# Adafruit_Feather_M0_Adalogger.net
KiCad netlist of a schematic drawn in EAGLE
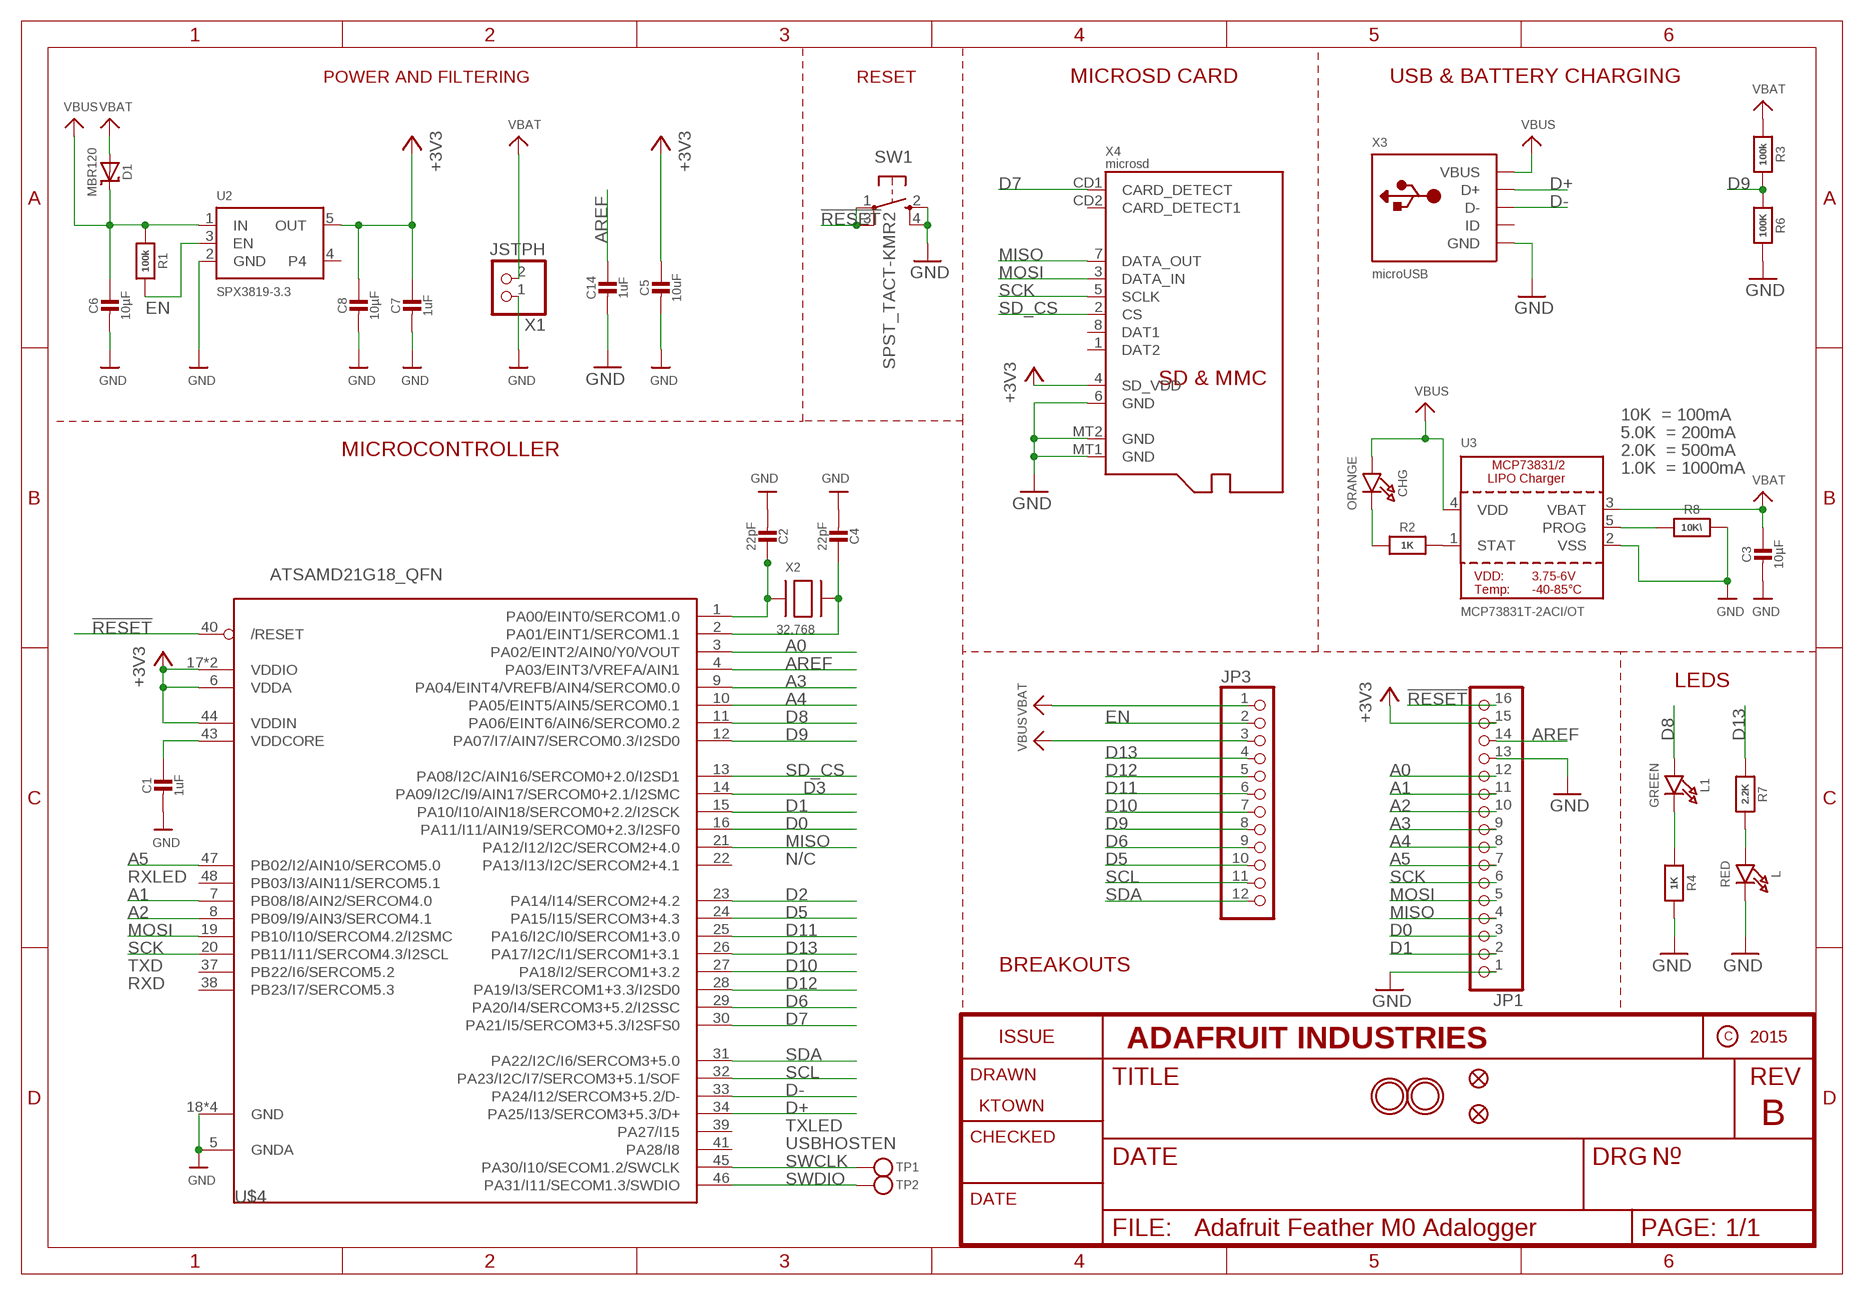
[diagram p0: schematic, sheet 1]

(export (version "E")
  (design (tool "Eeschema 10.0.6"))
  (components
    (comp (ref "C1")
      (value "1uF")
      (footprint "eagle-import:0603-NO")
      (libsource (lib "eagle-import") (part "CAP_CERAMIC0603_NO"))
    )
    (comp (ref "C2")
      (value "22pF")
      (footprint "eagle-import:0603-NO")
      (libsource (lib "eagle-import") (part "CAP_CERAMIC0603_NO"))
    )
    (comp (ref "C3")
      (value "10µF")
      (footprint "eagle-import:0805-NO")
      (libsource (lib "eagle-import") (part "CAP_CERAMIC0805-NOOUTLINE"))
    )
    (comp (ref "C4")
      (value "22pF")
      (footprint "eagle-import:0603-NO")
      (libsource (lib "eagle-import") (part "CAP_CERAMIC0603_NO"))
    )
    (comp (ref "C5")
      (value "10uF")
      (footprint "eagle-import:0805-NO")
      (libsource (lib "eagle-import") (part "CAP_CERAMIC0805-NOOUTLINE"))
    )
    (comp (ref "C6")
      (value "10µF")
      (footprint "eagle-import:0805-NO")
      (libsource (lib "eagle-import") (part "CAP_CERAMIC0805-NOOUTLINE"))
    )
    (comp (ref "C7")
      (value "1uF")
      (footprint "eagle-import:0603-NO")
      (libsource (lib "eagle-import") (part "CAP_CERAMIC0603_NO"))
    )
    (comp (ref "C8")
      (value "10µF")
      (footprint "eagle-import:0805-NO")
      (libsource (lib "eagle-import") (part "CAP_CERAMIC0805-NOOUTLINE"))
    )
    (comp (ref "C14")
      (value "1uF")
      (footprint "eagle-import:0603-NO")
      (libsource (lib "eagle-import") (part "CAP_CERAMIC0603_NO"))
    )
    (comp (ref "CHG")
      (value "ORANGE")
      (footprint "eagle-import:CHIPLED_0805_NOOUTLINE")
      (libsource (lib "eagle-import") (part "LED0805_NOOUTLINE"))
    )
    (comp (ref "D1")
      (value "MBR120")
      (footprint "eagle-import:SOD-123")
      (libsource (lib "eagle-import") (part "DIODE-SCHOTTKYSOD-123"))
    )
    (comp (ref "JP1")
      (value "HEADER-1X16ROUND")
      (footprint "eagle-import:1X16_ROUND")
      (libsource (lib "eagle-import") (part "HEADER-1X16ROUND"))
    )
    (comp (ref "JP3")
      (value "HEADER-1X12")
      (footprint "eagle-import:1X12_ROUND")
      (libsource (lib "eagle-import") (part "HEADER-1X12"))
    )
    (comp (ref "L")
      (value "RED")
      (footprint "eagle-import:CHIPLED_0805_NOOUTLINE")
      (libsource (lib "eagle-import") (part "LED0805_NOOUTLINE"))
    )
    (comp (ref "L1")
      (value "GREEN")
      (footprint "eagle-import:CHIPLED_0805_NOOUTLINE")
      (libsource (lib "eagle-import") (part "LED0805_NOOUTLINE"))
    )
    (comp (ref "R1")
      (value "100k")
      (footprint "eagle-import:0603-NO")
      (libsource (lib "eagle-import") (part "RESISTOR_0603_NOOUT"))
    )
    (comp (ref "R2")
      (value "1K")
      (footprint "eagle-import:0603-NO")
      (libsource (lib "eagle-import") (part "RESISTOR_0603_NOOUT"))
    )
    (comp (ref "R3")
      (value "100k")
      (footprint "eagle-import:0603-NO")
      (libsource (lib "eagle-import") (part "RESISTOR_0603_NOOUT"))
    )
    (comp (ref "R4")
      (value "1K")
      (footprint "eagle-import:0603-NO")
      (libsource (lib "eagle-import") (part "RESISTOR_0603_NOOUT"))
    )
    (comp (ref "R6")
      (value "100K")
      (footprint "eagle-import:0603-NO")
      (libsource (lib "eagle-import") (part "RESISTOR_0603_NOOUT"))
    )
    (comp (ref "R7")
      (value "2.2K")
      (footprint "eagle-import:0603-NO")
      (libsource (lib "eagle-import") (part "RESISTOR_0603_NOOUT"))
    )
    (comp (ref "R8")
      (value "10K\\")
      (footprint "eagle-import:0603-NO")
      (libsource (lib "eagle-import") (part "RESISTOR_0603_NOOUT"))
    )
    (comp (ref "SW1")
      (value "SPST_TACT-KMR2")
      (footprint "eagle-import:KMR2")
      (libsource (lib "eagle-import") (part "SPST_TACT-KMR2"))
    )
    (comp (ref "TP1")
      (value "TESTPOINTROUND1.5MM")
      (footprint "eagle-import:TESTPOINT_ROUND_1.5MM")
      (libsource (lib "eagle-import") (part "TESTPOINTROUND1.5MM"))
    )
    (comp (ref "TP2")
      (value "TESTPOINTROUND1.5MM")
      (footprint "eagle-import:TESTPOINT_ROUND_1.5MM")
      (libsource (lib "eagle-import") (part "TESTPOINTROUND1.5MM"))
    )
    (comp (ref "U$4")
      (value "ATSAMD21G18_QFN")
      (footprint "eagle-import:TQFN48_7MM")
      (libsource (lib "eagle-import") (part "ATSAMD21J_QFN"))
    )
    (comp (ref "U$31")
      (value "MOUNTINGHOLE2.5")
      (footprint "eagle-import:MOUNTINGHOLE_2.5_PLATED")
      (libsource (lib "eagle-import") (part "MOUNTINGHOLE2.5"))
    )
    (comp (ref "U$32")
      (value "MOUNTINGHOLE2.5")
      (footprint "eagle-import:MOUNTINGHOLE_2.5_PLATED")
      (libsource (lib "eagle-import") (part "MOUNTINGHOLE2.5"))
    )
    (comp (ref "U$34")
      (value "FIDUCIAL\"\"")
      (footprint "eagle-import:FIDUCIAL_1MM")
      (libsource (lib "eagle-import") (part "FIDUCIAL{dblquote}{dblquote}"))
    )
    (comp (ref "U$35")
      (value "FIDUCIAL\"\"")
      (footprint "eagle-import:FIDUCIAL_1MM")
      (libsource (lib "eagle-import") (part "FIDUCIAL{dblquote}{dblquote}"))
    )
    (comp (ref "U2")
      (value "SPX3819-3.3")
      (footprint "eagle-import:SOT23-5")
      (libsource (lib "eagle-import") (part "VREG_SOT23-5"))
    )
    (comp (ref "U3")
      (value "MCP73831T-2ACI/OT")
      (footprint "eagle-import:SOT23-5")
      (libsource (lib "eagle-import") (part "MCP73831/2"))
    )
    (comp (ref "X1")
      (value "JSTPH")
      (footprint "eagle-import:JSTPH2")
      (libsource (lib "eagle-import") (part "CON_JST_PH_2PIN"))
    )
    (comp (ref "X2")
      (value "32.768")
      (footprint "eagle-import:XTAL3215")
      (libsource (lib "eagle-import") (part "XTAL-3.2X1.5"))
    )
    (comp (ref "X3")
      (value "microUSB")
      (footprint "eagle-import:4UCONN_20329_V2")
      (libsource (lib "eagle-import") (part "USB_MICRO_20329_V2"))
    )
    (comp (ref "X4")
      (value "microsd")
      (footprint "eagle-import:MICROSD")
      (libsource (lib "eagle-import") (part "MICROSD"))
    )
  )
  (nets
    (net (code "1") (name "+3V3") (class "Default")
      (node (ref "C5") (pin "1") (pinfunction "1_1") (pintype "passive"))
      (node (ref "C7") (pin "1") (pinfunction "1_1") (pintype "passive"))
      (node (ref "C8") (pin "1") (pinfunction "1_1") (pintype "passive"))
      (node (ref "JP1") (pin "15") (pinfunction "15_15") (pintype "passive"))
      (node (ref "U$4") (pin "17") (pinfunction "VDDIO_17") (pintype "power_in"))
      (node (ref "U$4") (pin "36") (pinfunction "VDDIO_36") (pintype "power_in"))
      (node (ref "U$4") (pin "44") (pinfunction "VDDIN_44") (pintype "power_in"))
      (node (ref "U$4") (pin "6") (pinfunction "VDDA_6") (pintype "power_in"))
      (node (ref "U2") (pin "5") (pinfunction "OUT_5") (pintype "power_in"))
      (node (ref "X4") (pin "4") (pinfunction "SD_VDD_4") (pintype "power_in"))
    )
    (net (code "2") (name "/A0") (class "Default")
      (node (ref "JP1") (pin "12") (pinfunction "12_12") (pintype "passive"))
      (node (ref "U$4") (pin "3") (pinfunction "PA02/EINT2/AIN0/Y0/VOUT_3") (pintype "bidirectional"))
    )
    (net (code "3") (name "/A1") (class "Default")
      (node (ref "JP1") (pin "11") (pinfunction "11_11") (pintype "passive"))
      (node (ref "U$4") (pin "7") (pinfunction "PB08/I8/AIN2/SERCOM4.0_7") (pintype "bidirectional"))
    )
    (net (code "4") (name "/A2") (class "Default")
      (node (ref "JP1") (pin "10") (pinfunction "10_10") (pintype "passive"))
      (node (ref "U$4") (pin "8") (pinfunction "PB09/I9/AIN3/SERCOM4.1_8") (pintype "bidirectional"))
    )
    (net (code "5") (name "/A3") (class "Default")
      (node (ref "JP1") (pin "9") (pinfunction "9_9") (pintype "passive"))
      (node (ref "U$4") (pin "9") (pinfunction "PA04/EINT4/VREFB/AIN4/SERCOM0.0_9") (pintype "bidirectional"))
    )
    (net (code "6") (name "/A4") (class "Default")
      (node (ref "JP1") (pin "8") (pinfunction "8_8") (pintype "passive"))
      (node (ref "U$4") (pin "10") (pinfunction "PA05/EINT5/AIN5/SERCOM0.1_10") (pintype "bidirectional"))
    )
    (net (code "7") (name "/A5") (class "Default")
      (node (ref "JP1") (pin "7") (pinfunction "7_7") (pintype "passive"))
      (node (ref "U$4") (pin "47") (pinfunction "PB02/I2/AIN10/SERCOM5.0_47") (pintype "bidirectional"))
    )
    (net (code "8") (name "/AREF") (class "Default")
      (node (ref "C14") (pin "1") (pinfunction "1_1") (pintype "passive"))
      (node (ref "JP1") (pin "14") (pinfunction "14_14") (pintype "passive"))
      (node (ref "U$4") (pin "4") (pinfunction "PA03/EINT3/VREFA/AIN1_4") (pintype "bidirectional"))
    )
    (net (code "9") (name "/D+") (class "Default")
      (node (ref "U$4") (pin "34") (pinfunction "PA25/I13/SERCOM3+5.3/D+_34") (pintype "bidirectional"))
      (node (ref "X3") (pin "D+") (pinfunction "D+_D+") (pintype "bidirectional"))
    )
    (net (code "10") (name "/D-") (class "Default")
      (node (ref "U$4") (pin "33") (pinfunction "PA24/I12/SERCOM3+5.2/D-_33") (pintype "bidirectional"))
      (node (ref "X3") (pin "D-") (pinfunction "D-_D-") (pintype "bidirectional"))
    )
    (net (code "11") (name "/D0") (class "Default")
      (node (ref "JP1") (pin "3") (pinfunction "3_3") (pintype "passive"))
      (node (ref "U$4") (pin "16") (pinfunction "PA11/I11/AIN19/SERCOM0+2.3/I2SF0_16") (pintype "bidirectional"))
    )
    (net (code "12") (name "/D1") (class "Default")
      (node (ref "JP1") (pin "2") (pinfunction "2_2") (pintype "passive"))
      (node (ref "U$4") (pin "15") (pinfunction "PA10/I10/AIN18/SERCOM0+2.2/I2SCK_15") (pintype "bidirectional"))
    )
    (net (code "13") (name "/D2") (class "Default")
      (node (ref "U$4") (pin "23") (pinfunction "PA14/I14/SERCOM2+4.2_23") (pintype "bidirectional"))
    )
    (net (code "14") (name "/D3") (class "Default")
      (node (ref "U$4") (pin "14") (pinfunction "PA09/I2C/I9/AIN17/SERCOM0+2.1/I2SMC_14") (pintype "bidirectional"))
    )
    (net (code "15") (name "/D5") (class "Default")
      (node (ref "JP3") (pin "10") (pinfunction "10_10") (pintype "passive"))
      (node (ref "U$4") (pin "24") (pinfunction "PA15/I15/SERCOM3+4.3_24") (pintype "bidirectional"))
    )
    (net (code "16") (name "/D6") (class "Default")
      (node (ref "JP3") (pin "9") (pinfunction "9_9") (pintype "passive"))
      (node (ref "U$4") (pin "29") (pinfunction "PA20/I4/SERCOM3+5.2/I2SSC_29") (pintype "bidirectional"))
    )
    (net (code "17") (name "/D7") (class "Default")
      (node (ref "U$4") (pin "30") (pinfunction "PA21/I5/SERCOM3+5.3/I2SFS0_30") (pintype "bidirectional"))
      (node (ref "X4") (pin "CD1") (pinfunction "CARD_DETECT_CD1") (pintype "passive"))
    )
    (net (code "18") (name "/D8") (class "Default")
      (node (ref "L1") (pin "A") (pinfunction "A_A") (pintype "passive"))
      (node (ref "U$4") (pin "11") (pinfunction "PA06/EINT6/AIN6/SERCOM0.2_11") (pintype "bidirectional"))
    )
    (net (code "19") (name "/D9") (class "Default")
      (node (ref "JP3") (pin "8") (pinfunction "8_8") (pintype "passive"))
      (node (ref "R3") (pin "2") (pinfunction "2_2") (pintype "passive"))
      (node (ref "R6") (pin "1") (pinfunction "1_1") (pintype "passive"))
      (node (ref "U$4") (pin "12") (pinfunction "PA07/I7/AIN7/SERCOM0.3/I2SD0_12") (pintype "bidirectional"))
    )
    (net (code "20") (name "/D10") (class "Default")
      (node (ref "JP3") (pin "7") (pinfunction "7_7") (pintype "passive"))
      (node (ref "U$4") (pin "27") (pinfunction "PA18/I2/SERCOM1+3.2_27") (pintype "bidirectional"))
    )
    (net (code "21") (name "/D11") (class "Default")
      (node (ref "JP3") (pin "6") (pinfunction "6_6") (pintype "passive"))
      (node (ref "U$4") (pin "25") (pinfunction "PA16/I2C/I0/SERCOM1+3.0_25") (pintype "bidirectional"))
    )
    (net (code "22") (name "/D12") (class "Default")
      (node (ref "JP3") (pin "5") (pinfunction "5_5") (pintype "passive"))
      (node (ref "U$4") (pin "28") (pinfunction "PA19/I3/SERCOM1+3.3/I2SD0_28") (pintype "bidirectional"))
    )
    (net (code "23") (name "/D13") (class "Default")
      (node (ref "JP3") (pin "4") (pinfunction "4_4") (pintype "passive"))
      (node (ref "R7") (pin "1") (pinfunction "1_1") (pintype "passive"))
      (node (ref "U$4") (pin "26") (pinfunction "PA17/I2C/I1/SERCOM1+3.1_26") (pintype "bidirectional"))
    )
    (net (code "24") (name "/EN") (class "Default")
      (node (ref "JP3") (pin "2") (pinfunction "2_2") (pintype "passive"))
      (node (ref "R1") (pin "2") (pinfunction "2_2") (pintype "passive"))
      (node (ref "U2") (pin "3") (pinfunction "EN_3") (pintype "input"))
    )
    (net (code "25") (name "/MISO") (class "Default")
      (node (ref "JP1") (pin "4") (pinfunction "4_4") (pintype "passive"))
      (node (ref "U$4") (pin "21") (pinfunction "PA12/I12/I2C/SERCOM2+4.0_21") (pintype "bidirectional"))
      (node (ref "X4") (pin "7") (pinfunction "DATA_OUT_7") (pintype "output"))
    )
    (net (code "26") (name "/MOSI") (class "Default")
      (node (ref "JP1") (pin "5") (pinfunction "5_5") (pintype "passive"))
      (node (ref "U$4") (pin "19") (pinfunction "PB10/I10/SERCOM4.2/I2SMC_19") (pintype "bidirectional"))
      (node (ref "X4") (pin "3") (pinfunction "DATA_IN_3") (pintype "input"))
    )
    (net (code "27") (name "/SCK") (class "Default")
      (node (ref "JP1") (pin "6") (pinfunction "6_6") (pintype "passive"))
      (node (ref "U$4") (pin "20") (pinfunction "PB11/I11/SERCOM4.3/I2SCL_20") (pintype "bidirectional"))
      (node (ref "X4") (pin "5") (pinfunction "SCLK_5") (pintype "input"))
    )
    (net (code "28") (name "/SCL") (class "Default")
      (node (ref "JP3") (pin "11") (pinfunction "11_11") (pintype "passive"))
      (node (ref "U$4") (pin "32") (pinfunction "PA23/I2C/I7/SERCOM3+5.1/SOF_32") (pintype "bidirectional"))
    )
    (net (code "29") (name "/SDA") (class "Default")
      (node (ref "JP3") (pin "12") (pinfunction "12_12") (pintype "passive"))
      (node (ref "U$4") (pin "31") (pinfunction "PA22/I2C/I6/SERCOM3+5.0_31") (pintype "bidirectional"))
    )
    (net (code "30") (name "/SD_CS") (class "Default")
      (node (ref "U$4") (pin "13") (pinfunction "PA08/I2C/AIN16/SERCOM0+2.0/I2SD1_13") (pintype "bidirectional"))
      (node (ref "X4") (pin "2") (pinfunction "CS_2") (pintype "input"))
    )
    (net (code "31") (name "/SWCLK") (class "Default")
      (node (ref "TP1") (pin "P$1") (pinfunction "P$1_P$1") (pintype "bidirectional"))
      (node (ref "U$4") (pin "45") (pinfunction "PA30/I10/SECOM1.2/SWCLK_45") (pintype "bidirectional"))
    )
    (net (code "32") (name "/SWDIO") (class "Default")
      (node (ref "TP2") (pin "P$1") (pinfunction "P$1_P$1") (pintype "bidirectional"))
      (node (ref "U$4") (pin "46") (pinfunction "PA31/I11/SECOM1.3/SWDIO_46") (pintype "bidirectional"))
    )
    (net (code "33") (name "/~{RESET}") (class "Default")
      (node (ref "JP1") (pin "16") (pinfunction "16_16") (pintype "passive"))
      (node (ref "SW1") (pin "1") (pinfunction "P_1") (pintype "passive"))
      (node (ref "SW1") (pin "3") (pinfunction "P1_3") (pintype "passive"))
      (node (ref "U$4") (pin "40") (pinfunction "/RESET_40") (pintype "bidirectional"))
    )
    (net (code "34") (name "GND") (class "Default")
      (node (ref "C1") (pin "2") (pinfunction "2_2") (pintype "passive"))
      (node (ref "C14") (pin "2") (pinfunction "2_2") (pintype "passive"))
      (node (ref "C2") (pin "2") (pinfunction "2_2") (pintype "passive"))
      (node (ref "C3") (pin "2") (pinfunction "2_2") (pintype "passive"))
      (node (ref "C4") (pin "2") (pinfunction "2_2") (pintype "passive"))
      (node (ref "C5") (pin "2") (pinfunction "2_2") (pintype "passive"))
      (node (ref "C6") (pin "2") (pinfunction "2_2") (pintype "passive"))
      (node (ref "C7") (pin "2") (pinfunction "2_2") (pintype "passive"))
      (node (ref "C8") (pin "2") (pinfunction "2_2") (pintype "passive"))
      (node (ref "JP1") (pin "1") (pinfunction "1_1") (pintype "passive"))
      (node (ref "JP1") (pin "13") (pinfunction "13_13") (pintype "passive"))
      (node (ref "L") (pin "C") (pinfunction "C_C") (pintype "passive"))
      (node (ref "R4") (pin "2") (pinfunction "2_2") (pintype "passive"))
      (node (ref "R6") (pin "2") (pinfunction "2_2") (pintype "passive"))
      (node (ref "R8") (pin "2") (pinfunction "2_2") (pintype "passive"))
      (node (ref "SW1") (pin "2") (pinfunction "S_2") (pintype "passive"))
      (node (ref "SW1") (pin "4") (pinfunction "S1_4") (pintype "passive"))
      (node (ref "U$4") (pin "18") (pinfunction "GND_18") (pintype "power_in"))
      (node (ref "U$4") (pin "35") (pinfunction "GND_35") (pintype "power_in"))
      (node (ref "U$4") (pin "42") (pinfunction "GND_42") (pintype "power_in"))
      (node (ref "U$4") (pin "5") (pinfunction "GNDA_5") (pintype "power_in"))
      (node (ref "U$4") (pin "THERMAL") (pinfunction "GND_THERMAL") (pintype "power_in"))
      (node (ref "U2") (pin "2") (pinfunction "GND_2") (pintype "power_in"))
      (node (ref "U3") (pin "2") (pinfunction "VSS_2") (pintype "power_in"))
      (node (ref "X1") (pin "1") (pinfunction "1_1") (pintype "passive"))
      (node (ref "X3") (pin "BASE@1") (pinfunction "GND_BASE@1") (pintype "power_in"))
      (node (ref "X3") (pin "BASE@2") (pinfunction "GND_BASE@2") (pintype "power_in"))
      (node (ref "X3") (pin "GND") (pinfunction "GND_GND") (pintype "power_in"))
      (node (ref "X3") (pin "SPRT@1") (pinfunction "GND_SPRT@1") (pintype "power_in"))
      (node (ref "X3") (pin "SPRT@2") (pinfunction "GND_SPRT@2") (pintype "power_in"))
      (node (ref "X3") (pin "SPRT@3") (pinfunction "GND_SPRT@3") (pintype "power_in"))
      (node (ref "X3") (pin "SPRT@4") (pinfunction "GND_SPRT@4") (pintype "power_in"))
      (node (ref "X4") (pin "6") (pinfunction "GND_6") (pintype "power_in"))
      (node (ref "X4") (pin "MT1") (pinfunction "GND_MT1") (pintype "power_in"))
      (node (ref "X4") (pin "MT2") (pinfunction "GND_MT2") (pintype "power_in"))
    )
    (net (code "35") (name "Net-(CHG-PadC)") (class "Default")
      (node (ref "CHG") (pin "C") (pinfunction "C_C") (pintype "passive"))
      (node (ref "R2") (pin "1") (pinfunction "1_1") (pintype "passive"))
    )
    (net (code "36") (name "Net-(L-PadA)") (class "Default")
      (node (ref "L") (pin "A") (pinfunction "A_A") (pintype "passive"))
      (node (ref "R7") (pin "2") (pinfunction "2_2") (pintype "passive"))
    )
    (net (code "37") (name "Net-(L1-PadC)") (class "Default")
      (node (ref "L1") (pin "C") (pinfunction "C_C") (pintype "passive"))
      (node (ref "R4") (pin "1") (pinfunction "1_1") (pintype "passive"))
    )
    (net (code "38") (name "Net-(U$4-PA00{slash}EINT0{slash}SERCOM1.0)") (class "Default")
      (node (ref "C2") (pin "1") (pinfunction "1_1") (pintype "passive"))
      (node (ref "U$4") (pin "1") (pinfunction "PA00/EINT0/SERCOM1.0_1") (pintype "bidirectional"))
      (node (ref "X2") (pin "P$1") (pinfunction "P$1_P$1") (pintype "bidirectional"))
    )
    (net (code "39") (name "Net-(U$4-PA01{slash}EINT1{slash}SERCOM1.1)") (class "Default")
      (node (ref "C4") (pin "1") (pinfunction "1_1") (pintype "passive"))
      (node (ref "U$4") (pin "2") (pinfunction "PA01/EINT1/SERCOM1.1_2") (pintype "bidirectional"))
      (node (ref "X2") (pin "P$2") (pinfunction "P$2_P$2") (pintype "bidirectional"))
    )
    (net (code "40") (name "Net-(U$4-VDDCORE)") (class "Default")
      (node (ref "C1") (pin "1") (pinfunction "1_1") (pintype "passive"))
      (node (ref "U$4") (pin "43") (pinfunction "VDDCORE_43") (pintype "power_in"))
    )
    (net (code "41") (name "Net-(U3-PROG)") (class "Default")
      (node (ref "R8") (pin "1") (pinfunction "1_1") (pintype "passive"))
      (node (ref "U3") (pin "5") (pinfunction "PROG_5") (pintype "input"))
    )
    (net (code "42") (name "Net-(U3-STAT)") (class "Default")
      (node (ref "R2") (pin "2") (pinfunction "2_2") (pintype "passive"))
      (node (ref "U3") (pin "1") (pinfunction "STAT_1") (pintype "output"))
    )
    (net (code "43") (name "VBAT") (class "Default")
      (node (ref "C3") (pin "1") (pinfunction "1_1") (pintype "passive"))
      (node (ref "D1") (pin "A") (pinfunction "A_A") (pintype "passive"))
      (node (ref "JP3") (pin "1") (pinfunction "1_1") (pintype "passive"))
      (node (ref "R3") (pin "1") (pinfunction "1_1") (pintype "passive"))
      (node (ref "U3") (pin "3") (pinfunction "VBAT_3") (pintype "power_in"))
      (node (ref "X1") (pin "2") (pinfunction "2_2") (pintype "passive"))
    )
    (net (code "44") (name "VBUS") (class "Default")
      (node (ref "C6") (pin "1") (pinfunction "1_1") (pintype "passive"))
      (node (ref "CHG") (pin "A") (pinfunction "A_A") (pintype "passive"))
      (node (ref "D1") (pin "C") (pinfunction "C_C") (pintype "passive"))
      (node (ref "JP3") (pin "3") (pinfunction "3_3") (pintype "passive"))
      (node (ref "R1") (pin "1") (pinfunction "1_1") (pintype "passive"))
      (node (ref "U2") (pin "1") (pinfunction "IN_1") (pintype "power_in"))
      (node (ref "U3") (pin "4") (pinfunction "VDD_4") (pintype "power_in"))
      (node (ref "X3") (pin "VBUS") (pinfunction "VBUS_VBUS") (pintype "power_in"))
    )
    (net (code "45") (name "unconnected-(U$4-PA13{slash}I13{slash}I2C{slash}SERCOM2+4.1-Pad22)") (class "Default")
      (node (ref "U$4") (pin "22") (pinfunction "PA13/I13/I2C/SERCOM2+4.1_22") (pintype "bidirectional"))
    )
    (net (code "46") (name "unconnected-(U$4-PA27{slash}I15-Pad39)") (class "Default")
      (node (ref "U$4") (pin "39") (pinfunction "PA27/I15_39") (pintype "bidirectional"))
    )
    (net (code "47") (name "unconnected-(U$4-PA28{slash}I8-Pad41)") (class "Default")
      (node (ref "U$4") (pin "41") (pinfunction "PA28/I8_41") (pintype "bidirectional"))
    )
    (net (code "48") (name "unconnected-(U$4-PB03{slash}I3{slash}AIN11{slash}SERCOM5.1-Pad48)") (class "Default")
      (node (ref "U$4") (pin "48") (pinfunction "PB03/I3/AIN11/SERCOM5.1_48") (pintype "bidirectional"))
    )
    (net (code "49") (name "unconnected-(U$4-PB22{slash}I6{slash}SERCOM5.2-Pad37)") (class "Default")
      (node (ref "U$4") (pin "37") (pinfunction "PB22/I6/SERCOM5.2_37") (pintype "bidirectional"))
    )
    (net (code "50") (name "unconnected-(U$4-PB23{slash}I7{slash}SERCOM5.3-Pad38)") (class "Default")
      (node (ref "U$4") (pin "38") (pinfunction "PB23/I7/SERCOM5.3_38") (pintype "bidirectional"))
    )
    (net (code "51") (name "unconnected-(U2-P4-Pad4)") (class "Default")
      (node (ref "U2") (pin "4") (pinfunction "P4_4") (pintype "bidirectional"))
    )
    (net (code "52") (name "unconnected-(X3-PadID)") (class "Default")
      (node (ref "X3") (pin "ID") (pinfunction "ID_ID") (pintype "bidirectional"))
    )
    (net (code "53") (name "unconnected-(X4-CARD_DETECT1-PadCD2)") (class "Default")
      (node (ref "X4") (pin "CD2") (pinfunction "CARD_DETECT1_CD2") (pintype "passive"))
    )
    (net (code "54") (name "unconnected-(X4-DAT1-Pad8)") (class "Default")
      (node (ref "X4") (pin "8") (pinfunction "DAT1_8") (pintype "bidirectional"))
    )
    (net (code "55") (name "unconnected-(X4-DAT2-Pad1)") (class "Default")
      (node (ref "X4") (pin "1") (pinfunction "DAT2_1") (pintype "bidirectional"))
    )
  )
)
